# channel_1.net
KiCad netlist of a schematic drawn in Altium Designer
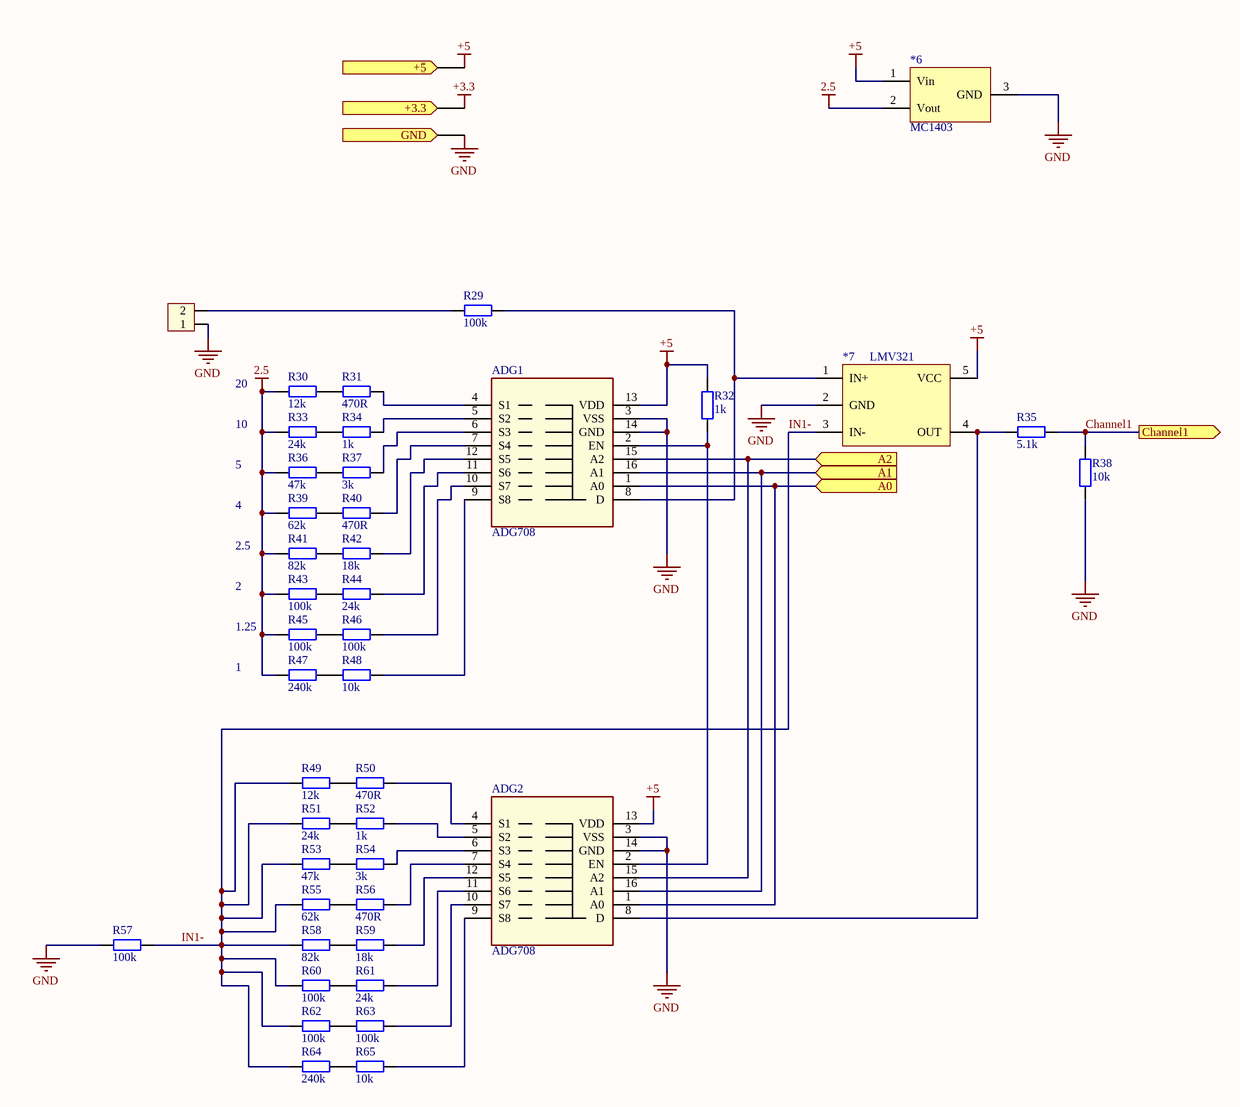
[diagram p0: channel_1.SchDoc]

(export (version "E")
  (design (tool "Eeschema 10.0.6"))
  (components
    (comp (ref "*6") (value "MC1403") (footprint "dip8") (libsource (lib "TrungVan_Lib") (part "MC1403")))
    (comp (ref "*7") (value "LMV321") (footprint "SOT23-5") (libsource (lib "TrungVan_Lib") (part "LMV321")))
    (comp (ref "ADG1")
      (value "ADG708")
      (footprint "TSSOP16")
      (libsource (lib "TrungVan_Lib") (part "ADG708"))
    )
    (comp (ref "ADG2")
      (value "ADG708")
      (footprint "TSSOP16")
      (libsource (lib "TrungVan_Lib") (part "ADG708"))
    )
    (comp (ref "H1")
      (value "Header 2P 2.54 Duc Thang")
      (footprint "15EDGR-3.81-2P")
      (description "Cắm")
      (libsource (lib "TrungVan_Lib") (part "Header 2P 2.54 Duc Thang"))
    )
    (comp (ref "R29")
      (value "100k")
      (footprint "tro smd 0603")
      (description "Dán")
      (libsource (lib "TrungVan_Lib") (part "Tro 2512 5% 100k"))
    )
    (comp (ref "R30")
      (value "12k")
      (footprint "tro smd 0603")
      (description "Dán")
      (libsource (lib "TrungVan_Lib") (part "Tro 0603 1% 10k"))
    )
    (comp (ref "R31")
      (value "470R")
      (footprint "tro smd 0603")
      (description "Dán")
      (libsource (lib "TrungVan_Lib") (part "Tro 0603 1% 10k"))
    )
    (comp (ref "R32")
      (value "1k")
      (footprint "tro smd 0603")
      (description "Dán")
      (libsource (lib "TrungVan_Lib") (part "Tro 0603 1% 10k"))
    )
    (comp (ref "R33")
      (value "24k")
      (footprint "tro smd 0603")
      (description "Dán")
      (libsource (lib "TrungVan_Lib") (part "Tro 0603 1% 10k"))
    )
    (comp (ref "R34")
      (value "1k")
      (footprint "tro smd 0603")
      (description "Dán")
      (libsource (lib "TrungVan_Lib") (part "Tro 0603 1% 10k"))
    )
    (comp (ref "R35")
      (value "5.1k")
      (footprint "tro smd 0603")
      (description "Dán")
      (libsource (lib "TrungVan_Lib") (part "Tro 0603 1% 10k"))
    )
    (comp (ref "R36")
      (value "47k")
      (footprint "tro smd 0603")
      (description "Dán")
      (libsource (lib "TrungVan_Lib") (part "Tro 0603 1% 10k"))
    )
    (comp (ref "R37")
      (value "3k")
      (footprint "tro smd 0603")
      (description "Dán")
      (libsource (lib "TrungVan_Lib") (part "Tro 0603 1% 10k"))
    )
    (comp (ref "R38")
      (value "10k")
      (footprint "tro smd 0603")
      (description "Dán")
      (libsource (lib "TrungVan_Lib") (part "Tro 0603 1% 10k"))
    )
    (comp (ref "R39")
      (value "62k")
      (footprint "tro smd 0603")
      (description "Dán")
      (libsource (lib "TrungVan_Lib") (part "Tro 0603 1% 10k"))
    )
    (comp (ref "R40")
      (value "470R")
      (footprint "tro smd 0603")
      (description "Dán")
      (libsource (lib "TrungVan_Lib") (part "Tro 0603 1% 10k"))
    )
    (comp (ref "R41")
      (value "82k")
      (footprint "tro smd 0603")
      (description "Dán")
      (libsource (lib "TrungVan_Lib") (part "Tro 0603 1% 10k"))
    )
    (comp (ref "R42")
      (value "18k")
      (footprint "tro smd 0603")
      (description "Dán")
      (libsource (lib "TrungVan_Lib") (part "Tro 0603 1% 10k"))
    )
    (comp (ref "R43")
      (value "100k")
      (footprint "tro smd 0603")
      (description "Dán")
      (libsource (lib "TrungVan_Lib") (part "Tro 2512 5% 100k"))
    )
    (comp (ref "R44")
      (value "24k")
      (footprint "tro smd 0603")
      (description "Dán")
      (libsource (lib "TrungVan_Lib") (part "Tro 0603 1% 10k"))
    )
    (comp (ref "R45")
      (value "100k")
      (footprint "tro smd 0603")
      (description "Dán")
      (libsource (lib "TrungVan_Lib") (part "Tro 2512 5% 100k"))
    )
    (comp (ref "R46")
      (value "100k")
      (footprint "tro smd 0603")
      (description "Dán")
      (libsource (lib "TrungVan_Lib") (part "Tro 2512 5% 100k"))
    )
    (comp (ref "R47")
      (value "240k")
      (footprint "tro smd 0603")
      (description "Dán")
      (libsource (lib "TrungVan_Lib") (part "Tro 2512 5% 100k"))
    )
    (comp (ref "R48")
      (value "10k")
      (footprint "tro smd 0603")
      (description "Dán")
      (libsource (lib "TrungVan_Lib") (part "Tro 2512 5% 100k"))
    )
    (comp (ref "R49")
      (value "12k")
      (footprint "tro smd 0603")
      (description "Dán")
      (libsource (lib "TrungVan_Lib") (part "Tro 0603 1% 10k"))
    )
    (comp (ref "R50")
      (value "470R")
      (footprint "tro smd 0603")
      (description "Dán")
      (libsource (lib "TrungVan_Lib") (part "Tro 0603 1% 10k"))
    )
    (comp (ref "R51")
      (value "24k")
      (footprint "tro smd 0603")
      (description "Dán")
      (libsource (lib "TrungVan_Lib") (part "Tro 0603 1% 10k"))
    )
    (comp (ref "R52")
      (value "1k")
      (footprint "tro smd 0603")
      (description "Dán")
      (libsource (lib "TrungVan_Lib") (part "Tro 0603 1% 10k"))
    )
    (comp (ref "R53")
      (value "47k")
      (footprint "tro smd 0603")
      (description "Dán")
      (libsource (lib "TrungVan_Lib") (part "Tro 0603 1% 10k"))
    )
    (comp (ref "R54")
      (value "3k")
      (footprint "tro smd 0603")
      (description "Dán")
      (libsource (lib "TrungVan_Lib") (part "Tro 0603 1% 10k"))
    )
    (comp (ref "R55")
      (value "62k")
      (footprint "tro smd 0603")
      (description "Dán")
      (libsource (lib "TrungVan_Lib") (part "Tro 0603 1% 10k"))
    )
    (comp (ref "R56")
      (value "470R")
      (footprint "tro smd 0603")
      (description "Dán")
      (libsource (lib "TrungVan_Lib") (part "Tro 0603 1% 10k"))
    )
    (comp (ref "R57")
      (value "100k")
      (footprint "tro smd 0603")
      (description "Dán")
      (libsource (lib "TrungVan_Lib") (part "Tro 2512 5% 100k"))
    )
    (comp (ref "R58")
      (value "82k")
      (footprint "tro smd 0603")
      (description "Dán")
      (libsource (lib "TrungVan_Lib") (part "Tro 0603 1% 10k"))
    )
    (comp (ref "R59")
      (value "18k")
      (footprint "tro smd 0603")
      (description "Dán")
      (libsource (lib "TrungVan_Lib") (part "Tro 0603 1% 10k"))
    )
    (comp (ref "R60")
      (value "100k")
      (footprint "tro smd 0603")
      (description "Dán")
      (libsource (lib "TrungVan_Lib") (part "Tro 2512 5% 100k"))
    )
    (comp (ref "R61")
      (value "24k")
      (footprint "tro smd 0603")
      (description "Dán")
      (libsource (lib "TrungVan_Lib") (part "Tro 0603 1% 10k"))
    )
    (comp (ref "R62")
      (value "100k")
      (footprint "tro smd 0603")
      (description "Dán")
      (libsource (lib "TrungVan_Lib") (part "Tro 2512 5% 100k"))
    )
    (comp (ref "R63")
      (value "100k")
      (footprint "tro smd 0603")
      (description "Dán")
      (libsource (lib "TrungVan_Lib") (part "Tro 2512 5% 100k"))
    )
    (comp (ref "R64")
      (value "240k")
      (footprint "tro smd 0603")
      (description "Dán")
      (libsource (lib "TrungVan_Lib") (part "Tro 2512 5% 100k"))
    )
    (comp (ref "R65")
      (value "10k")
      (footprint "tro smd 0603")
      (description "Dán")
      (libsource (lib "TrungVan_Lib") (part "Tro 2512 5% 100k"))
    )
  )
  (nets
    (net (code "2") (name "+5") (class "Default")
      (node (ref "*6") (pin "1") (pinfunction "Vin_1") (pintype "passive"))
      (node (ref "*7") (pin "5") (pinfunction "VCC_5") (pintype "passive"))
      (node (ref "ADG1") (pin "13") (pinfunction "VDD_13") (pintype "passive"))
      (node (ref "ADG2") (pin "13") (pinfunction "VDD_13") (pintype "passive"))
      (node (ref "R32") (pin "2") (pinfunction "2_2") (pintype "passive"))
    )
    (net (code "3") (name "/A0") (class "Default")
      (node (ref "ADG1") (pin "1") (pinfunction "A0_1") (pintype "passive"))
      (node (ref "ADG2") (pin "1") (pinfunction "A0_1") (pintype "passive"))
    )
    (net (code "4") (name "/A1") (class "Default")
      (node (ref "ADG1") (pin "16") (pinfunction "A1_16") (pintype "passive"))
      (node (ref "ADG2") (pin "16") (pinfunction "A1_16") (pintype "passive"))
    )
    (net (code "5") (name "/A2") (class "Default")
      (node (ref "ADG1") (pin "15") (pinfunction "A2_15") (pintype "passive"))
      (node (ref "ADG2") (pin "15") (pinfunction "A2_15") (pintype "passive"))
    )
    (net (code "6") (name "/Channel1") (class "Default")
      (node (ref "R35") (pin "2") (pinfunction "2_2") (pintype "passive"))
      (node (ref "R38") (pin "2") (pinfunction "2_2") (pintype "passive"))
    )
    (net (code "7") (name "/IN1-") (class "Default")
      (node (ref "*7") (pin "3") (pinfunction "IN-_3") (pintype "passive"))
      (node (ref "R49") (pin "1") (pinfunction "1_1") (pintype "passive"))
      (node (ref "R51") (pin "1") (pinfunction "1_1") (pintype "passive"))
      (node (ref "R53") (pin "1") (pinfunction "1_1") (pintype "passive"))
      (node (ref "R55") (pin "1") (pinfunction "1_1") (pintype "passive"))
      (node (ref "R57") (pin "1") (pinfunction "1_1") (pintype "passive"))
      (node (ref "R58") (pin "1") (pinfunction "1_1") (pintype "passive"))
      (node (ref "R60") (pin "2") (pinfunction "2_2") (pintype "passive"))
      (node (ref "R62") (pin "2") (pinfunction "2_2") (pintype "passive"))
      (node (ref "R64") (pin "2") (pinfunction "2_2") (pintype "passive"))
    )
    (net (code "8") (name "2.5") (class "Default")
      (node (ref "*6") (pin "2") (pinfunction "Vout_2") (pintype "passive"))
      (node (ref "R30") (pin "1") (pinfunction "1_1") (pintype "passive"))
      (node (ref "R33") (pin "1") (pinfunction "1_1") (pintype "passive"))
      (node (ref "R36") (pin "1") (pinfunction "1_1") (pintype "passive"))
      (node (ref "R39") (pin "1") (pinfunction "1_1") (pintype "passive"))
      (node (ref "R41") (pin "1") (pinfunction "1_1") (pintype "passive"))
      (node (ref "R43") (pin "2") (pinfunction "2_2") (pintype "passive"))
      (node (ref "R45") (pin "2") (pinfunction "2_2") (pintype "passive"))
      (node (ref "R47") (pin "2") (pinfunction "2_2") (pintype "passive"))
    )
    (net (code "9") (name "GND") (class "Default")
      (node (ref "*6") (pin "3") (pinfunction "GND_3") (pintype "passive"))
      (node (ref "*7") (pin "2") (pinfunction "GND_2") (pintype "passive"))
      (node (ref "ADG1") (pin "14") (pinfunction "GND_14") (pintype "passive"))
      (node (ref "ADG1") (pin "3") (pinfunction "VSS_3") (pintype "passive"))
      (node (ref "ADG2") (pin "14") (pinfunction "GND_14") (pintype "passive"))
      (node (ref "ADG2") (pin "3") (pinfunction "VSS_3") (pintype "passive"))
      (node (ref "H1") (pin "1") (pinfunction "1_1") (pintype "passive"))
      (node (ref "R38") (pin "1") (pinfunction "1_1") (pintype "passive"))
      (node (ref "R57") (pin "2") (pinfunction "2_2") (pintype "passive"))
    )
    (net (code "10") (name "Net-(*7-IN+)") (class "Default")
      (node (ref "*7") (pin "1") (pinfunction "IN+_1") (pintype "passive"))
      (node (ref "ADG1") (pin "8") (pinfunction "D_8") (pintype "passive"))
      (node (ref "R29") (pin "2") (pinfunction "2_2") (pintype "passive"))
    )
    (net (code "11") (name "Net-(*7-OUT)") (class "Default")
      (node (ref "*7") (pin "4") (pinfunction "OUT_4") (pintype "passive"))
      (node (ref "ADG2") (pin "8") (pinfunction "D_8") (pintype "passive"))
      (node (ref "R35") (pin "1") (pinfunction "1_1") (pintype "passive"))
    )
    (net (code "12") (name "Net-(ADG1-EN)") (class "Default")
      (node (ref "ADG1") (pin "2") (pinfunction "EN_2") (pintype "passive"))
      (node (ref "ADG2") (pin "2") (pinfunction "EN_2") (pintype "passive"))
      (node (ref "R32") (pin "1") (pinfunction "1_1") (pintype "passive"))
    )
    (net (code "13") (name "Net-(ADG1-S1)") (class "Default")
      (node (ref "ADG1") (pin "4") (pinfunction "S1_4") (pintype "passive"))
      (node (ref "R31") (pin "2") (pinfunction "2_2") (pintype "passive"))
    )
    (net (code "14") (name "Net-(ADG1-S2)") (class "Default")
      (node (ref "ADG1") (pin "5") (pinfunction "S2_5") (pintype "passive"))
      (node (ref "R34") (pin "2") (pinfunction "2_2") (pintype "passive"))
    )
    (net (code "15") (name "Net-(ADG1-S3)") (class "Default")
      (node (ref "ADG1") (pin "6") (pinfunction "S3_6") (pintype "passive"))
      (node (ref "R37") (pin "2") (pinfunction "2_2") (pintype "passive"))
    )
    (net (code "16") (name "Net-(ADG1-S4)") (class "Default")
      (node (ref "ADG1") (pin "7") (pinfunction "S4_7") (pintype "passive"))
      (node (ref "R40") (pin "2") (pinfunction "2_2") (pintype "passive"))
    )
    (net (code "17") (name "Net-(ADG1-S5)") (class "Default")
      (node (ref "ADG1") (pin "12") (pinfunction "S5_12") (pintype "passive"))
      (node (ref "R42") (pin "2") (pinfunction "2_2") (pintype "passive"))
    )
    (net (code "18") (name "Net-(ADG1-S6)") (class "Default")
      (node (ref "ADG1") (pin "11") (pinfunction "S6_11") (pintype "passive"))
      (node (ref "R44") (pin "2") (pinfunction "2_2") (pintype "passive"))
    )
    (net (code "19") (name "Net-(ADG1-S7)") (class "Default")
      (node (ref "ADG1") (pin "10") (pinfunction "S7_10") (pintype "passive"))
      (node (ref "R46") (pin "1") (pinfunction "1_1") (pintype "passive"))
    )
    (net (code "20") (name "Net-(ADG1-S8)") (class "Default")
      (node (ref "ADG1") (pin "9") (pinfunction "S8_9") (pintype "passive"))
      (node (ref "R48") (pin "1") (pinfunction "1_1") (pintype "passive"))
    )
    (net (code "21") (name "Net-(ADG2-S1)") (class "Default")
      (node (ref "ADG2") (pin "4") (pinfunction "S1_4") (pintype "passive"))
      (node (ref "R50") (pin "2") (pinfunction "2_2") (pintype "passive"))
    )
    (net (code "22") (name "Net-(ADG2-S2)") (class "Default")
      (node (ref "ADG2") (pin "5") (pinfunction "S2_5") (pintype "passive"))
      (node (ref "R52") (pin "2") (pinfunction "2_2") (pintype "passive"))
    )
    (net (code "23") (name "Net-(ADG2-S3)") (class "Default")
      (node (ref "ADG2") (pin "6") (pinfunction "S3_6") (pintype "passive"))
      (node (ref "R54") (pin "2") (pinfunction "2_2") (pintype "passive"))
    )
    (net (code "24") (name "Net-(ADG2-S4)") (class "Default")
      (node (ref "ADG2") (pin "7") (pinfunction "S4_7") (pintype "passive"))
      (node (ref "R56") (pin "2") (pinfunction "2_2") (pintype "passive"))
    )
    (net (code "25") (name "Net-(ADG2-S5)") (class "Default")
      (node (ref "ADG2") (pin "12") (pinfunction "S5_12") (pintype "passive"))
      (node (ref "R59") (pin "2") (pinfunction "2_2") (pintype "passive"))
    )
    (net (code "26") (name "Net-(ADG2-S6)") (class "Default")
      (node (ref "ADG2") (pin "11") (pinfunction "S6_11") (pintype "passive"))
      (node (ref "R61") (pin "2") (pinfunction "2_2") (pintype "passive"))
    )
    (net (code "27") (name "Net-(ADG2-S7)") (class "Default")
      (node (ref "ADG2") (pin "10") (pinfunction "S7_10") (pintype "passive"))
      (node (ref "R63") (pin "1") (pinfunction "1_1") (pintype "passive"))
    )
    (net (code "28") (name "Net-(ADG2-S8)") (class "Default")
      (node (ref "ADG2") (pin "9") (pinfunction "S8_9") (pintype "passive"))
      (node (ref "R65") (pin "1") (pinfunction "1_1") (pintype "passive"))
    )
    (net (code "29") (name "Net-(H1-Pad2)") (class "Default")
      (node (ref "H1") (pin "2") (pinfunction "2_2") (pintype "passive"))
      (node (ref "R29") (pin "1") (pinfunction "1_1") (pintype "passive"))
    )
    (net (code "30") (name "Net-(R30-Pad2)") (class "Default")
      (node (ref "R30") (pin "2") (pinfunction "2_2") (pintype "passive"))
      (node (ref "R31") (pin "1") (pinfunction "1_1") (pintype "passive"))
    )
    (net (code "31") (name "Net-(R33-Pad2)") (class "Default")
      (node (ref "R33") (pin "2") (pinfunction "2_2") (pintype "passive"))
      (node (ref "R34") (pin "1") (pinfunction "1_1") (pintype "passive"))
    )
    (net (code "32") (name "Net-(R36-Pad2)") (class "Default")
      (node (ref "R36") (pin "2") (pinfunction "2_2") (pintype "passive"))
      (node (ref "R37") (pin "1") (pinfunction "1_1") (pintype "passive"))
    )
    (net (code "33") (name "Net-(R39-Pad2)") (class "Default")
      (node (ref "R39") (pin "2") (pinfunction "2_2") (pintype "passive"))
      (node (ref "R40") (pin "1") (pinfunction "1_1") (pintype "passive"))
    )
    (net (code "34") (name "Net-(R41-Pad2)") (class "Default")
      (node (ref "R41") (pin "2") (pinfunction "2_2") (pintype "passive"))
      (node (ref "R42") (pin "1") (pinfunction "1_1") (pintype "passive"))
    )
    (net (code "35") (name "Net-(R43-Pad1)") (class "Default")
      (node (ref "R43") (pin "1") (pinfunction "1_1") (pintype "passive"))
      (node (ref "R44") (pin "1") (pinfunction "1_1") (pintype "passive"))
    )
    (net (code "36") (name "Net-(R45-Pad1)") (class "Default")
      (node (ref "R45") (pin "1") (pinfunction "1_1") (pintype "passive"))
      (node (ref "R46") (pin "2") (pinfunction "2_2") (pintype "passive"))
    )
    (net (code "37") (name "Net-(R47-Pad1)") (class "Default")
      (node (ref "R47") (pin "1") (pinfunction "1_1") (pintype "passive"))
      (node (ref "R48") (pin "2") (pinfunction "2_2") (pintype "passive"))
    )
    (net (code "38") (name "Net-(R49-Pad2)") (class "Default")
      (node (ref "R49") (pin "2") (pinfunction "2_2") (pintype "passive"))
      (node (ref "R50") (pin "1") (pinfunction "1_1") (pintype "passive"))
    )
    (net (code "39") (name "Net-(R51-Pad2)") (class "Default")
      (node (ref "R51") (pin "2") (pinfunction "2_2") (pintype "passive"))
      (node (ref "R52") (pin "1") (pinfunction "1_1") (pintype "passive"))
    )
    (net (code "40") (name "Net-(R53-Pad2)") (class "Default")
      (node (ref "R53") (pin "2") (pinfunction "2_2") (pintype "passive"))
      (node (ref "R54") (pin "1") (pinfunction "1_1") (pintype "passive"))
    )
    (net (code "41") (name "Net-(R55-Pad2)") (class "Default")
      (node (ref "R55") (pin "2") (pinfunction "2_2") (pintype "passive"))
      (node (ref "R56") (pin "1") (pinfunction "1_1") (pintype "passive"))
    )
    (net (code "42") (name "Net-(R58-Pad2)") (class "Default")
      (node (ref "R58") (pin "2") (pinfunction "2_2") (pintype "passive"))
      (node (ref "R59") (pin "1") (pinfunction "1_1") (pintype "passive"))
    )
    (net (code "43") (name "Net-(R60-Pad1)") (class "Default")
      (node (ref "R60") (pin "1") (pinfunction "1_1") (pintype "passive"))
      (node (ref "R61") (pin "1") (pinfunction "1_1") (pintype "passive"))
    )
    (net (code "44") (name "Net-(R62-Pad1)") (class "Default")
      (node (ref "R62") (pin "1") (pinfunction "1_1") (pintype "passive"))
      (node (ref "R63") (pin "2") (pinfunction "2_2") (pintype "passive"))
    )
    (net (code "45") (name "Net-(R64-Pad1)") (class "Default")
      (node (ref "R64") (pin "1") (pinfunction "1_1") (pintype "passive"))
      (node (ref "R65") (pin "2") (pinfunction "2_2") (pintype "passive"))
    )
  )
)
